# 16V2_EDA.net
KiCad netlist of a schematic drawn in EasyEDA Pro
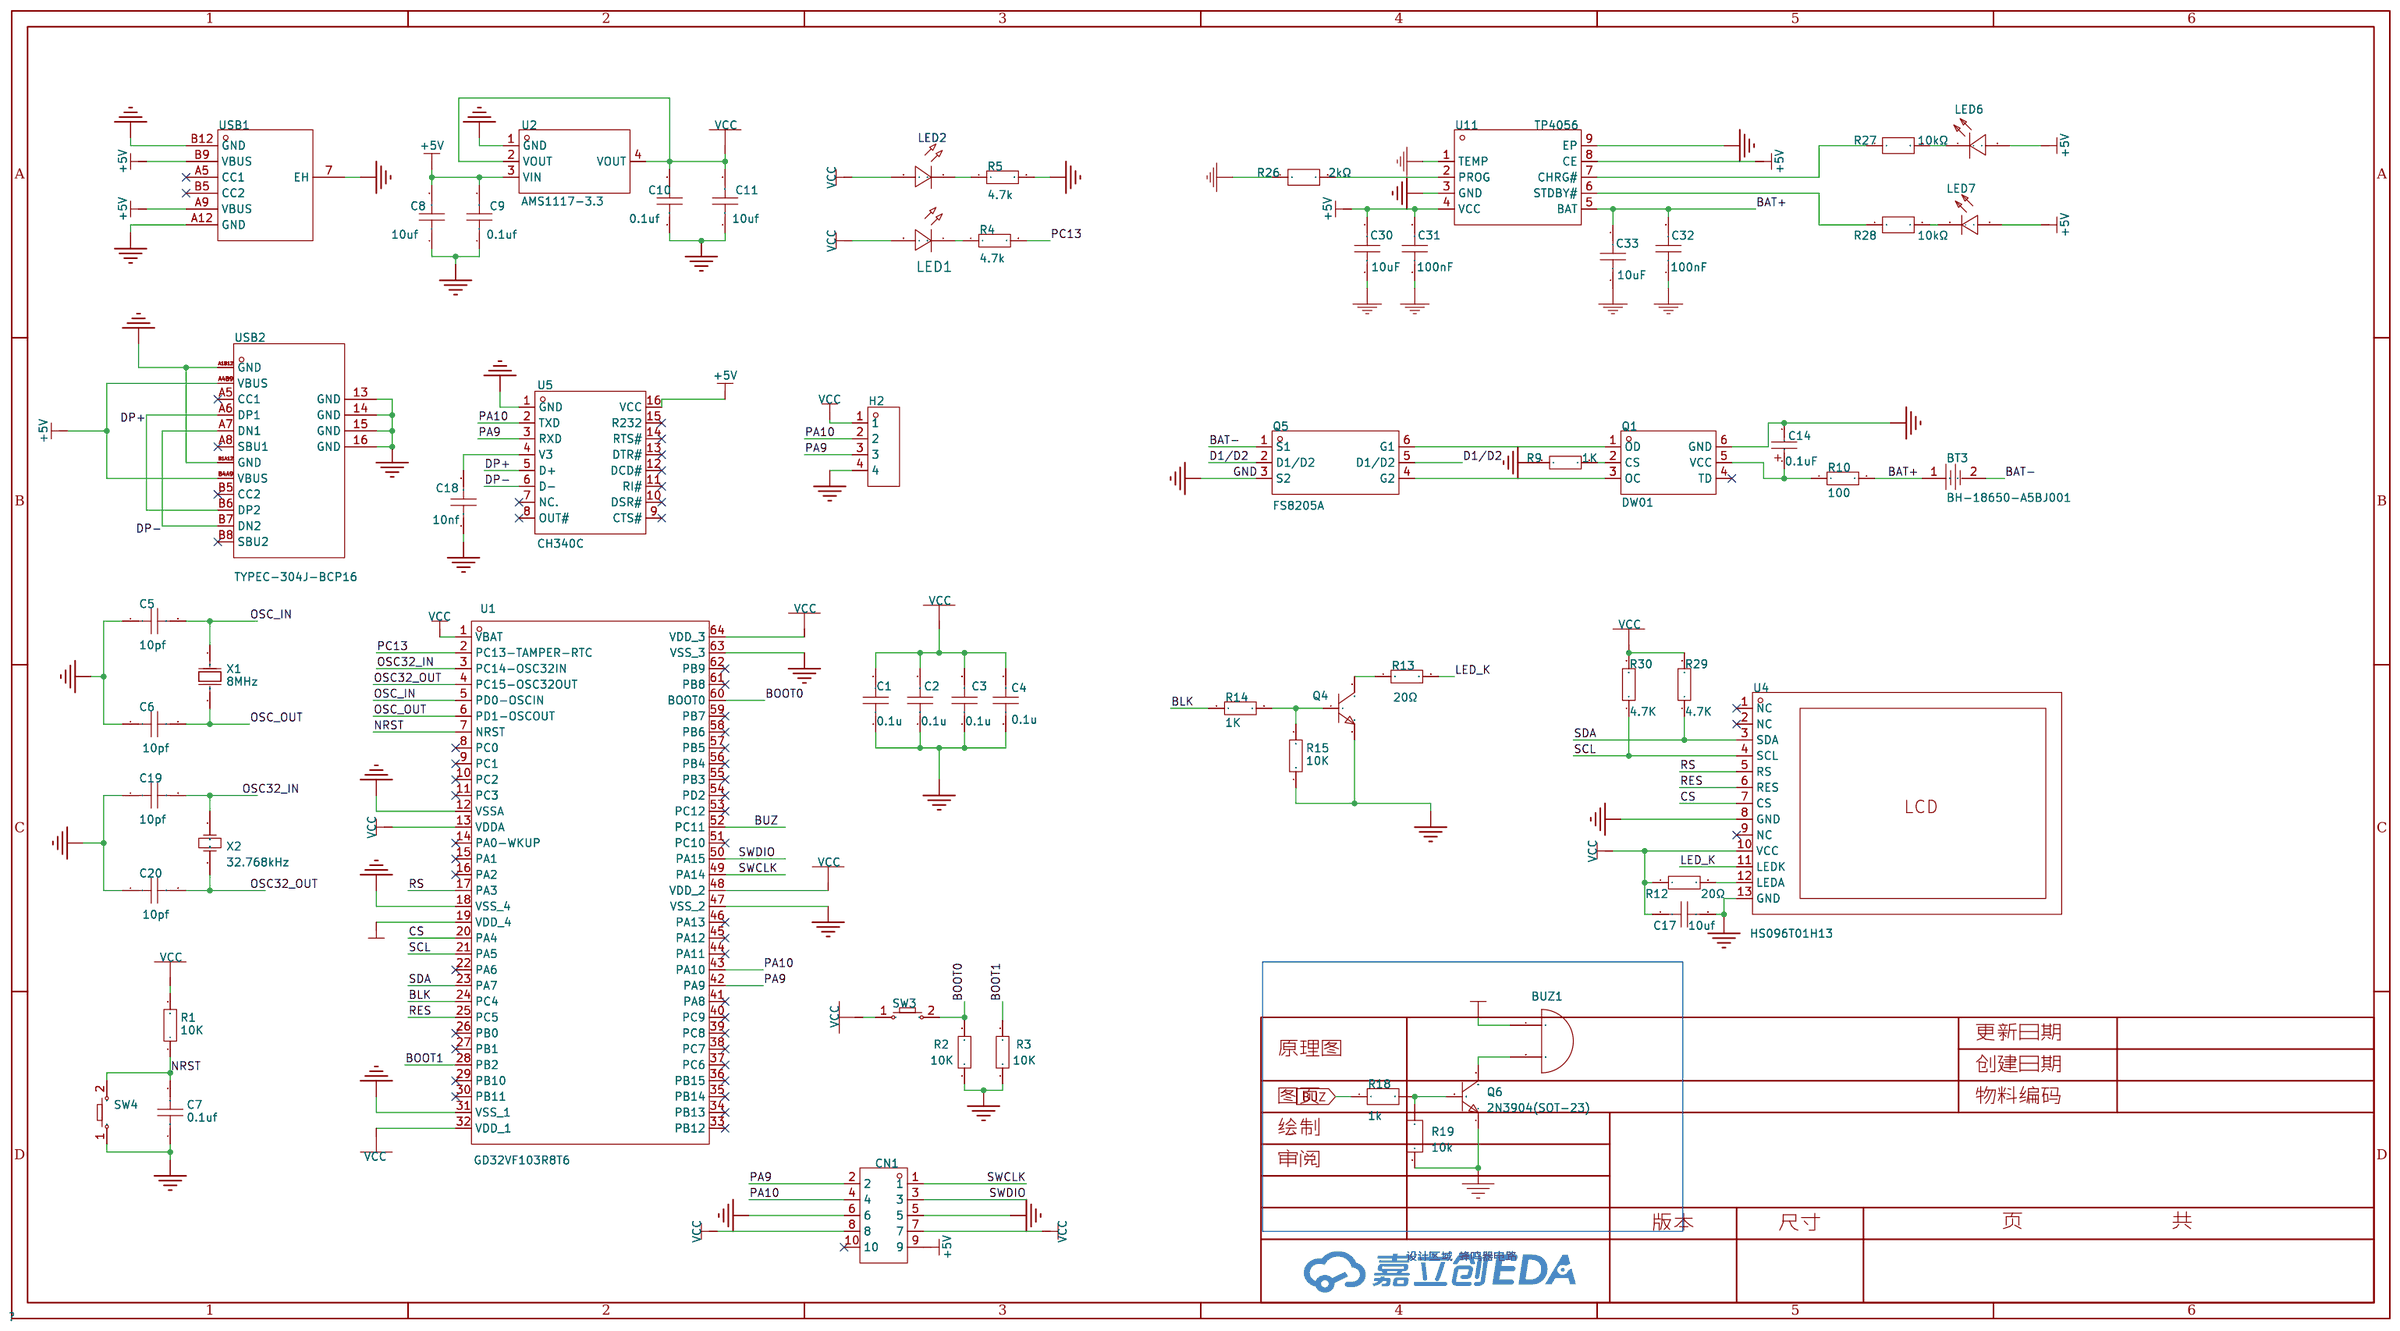
[diagram p0: schematic sheet]

(export (version "E")
  (design (tool "Eeschema 10.0.6"))
  (components
    (comp (ref "BT3")
      (value "BH-18650-A5BJ001")
      (footprint "easyedapro:BAT-TH_18650-A5BJ001")
      (description "BHNi DIP 适用电池18650电芯//电池底座/卧式DIP 电池盒/电池座 材质：PP  镀镍 ，")
      (fields (field (name "Manufacturer") "MYOUNG(美阳)"))
      (libsource (lib "easyedapro") (part "BH-18650-A5BJ001"))
    )
    (comp (ref "BUZ1") (value "BUZ1") (libsource (lib "easyedapro") (part "BUZ1")))
    (comp (ref "C1")
      (value "0.1u")
      (footprint "easyedapro:C0603")
      (libsource (lib "easyedapro") (part "capacitance"))
    )
    (comp (ref "C2")
      (value "0.1u")
      (footprint "easyedapro:C0603")
      (libsource (lib "easyedapro") (part "capacitance"))
    )
    (comp (ref "C3")
      (value "0.1u")
      (footprint "easyedapro:C0603")
      (libsource (lib "easyedapro") (part "capacitance"))
    )
    (comp (ref "C4")
      (value "0.1u")
      (footprint "easyedapro:C0603")
      (libsource (lib "easyedapro") (part "capacitance"))
    )
    (comp (ref "C5")
      (value "10pf")
      (footprint "easyedapro:C0603")
      (libsource (lib "easyedapro") (part "capacitance"))
    )
    (comp (ref "C6")
      (value "10pf")
      (footprint "easyedapro:C0603")
      (libsource (lib "easyedapro") (part "capacitance"))
    )
    (comp (ref "C7")
      (value "0.1uf")
      (footprint "easyedapro:C0603")
      (libsource (lib "easyedapro") (part "capacitance"))
    )
    (comp (ref "C8")
      (value "10uf")
      (footprint "easyedapro:C0603")
      (libsource (lib "easyedapro") (part "capacitance"))
    )
    (comp (ref "C9")
      (value "0.1uf")
      (footprint "easyedapro:C0603")
      (libsource (lib "easyedapro") (part "capacitance"))
    )
    (comp (ref "C10")
      (value "0.1uf")
      (footprint "easyedapro:C0603")
      (libsource (lib "easyedapro") (part "capacitance"))
    )
    (comp (ref "C11")
      (value "10uf")
      (footprint "easyedapro:C0603")
      (libsource (lib "easyedapro") (part "capacitance"))
    )
    (comp (ref "C14")
      (value "0.1uF")
      (footprint "easyedapro:C_Ele_SMD_3x5.4mm")
      (libsource (lib "easyedapro") (part "CAP"))
    )
    (comp (ref "C17")
      (value "10uf")
      (footprint "easyedapro:C0603")
      (libsource (lib "easyedapro") (part "capacitance"))
    )
    (comp (ref "C18")
      (value "10nf")
      (footprint "easyedapro:C0603")
      (libsource (lib "easyedapro") (part "capacitance"))
    )
    (comp (ref "C19")
      (value "10pf")
      (footprint "easyedapro:C0603")
      (libsource (lib "easyedapro") (part "capacitance"))
    )
    (comp (ref "C20")
      (value "10pf")
      (footprint "easyedapro:C0603")
      (libsource (lib "easyedapro") (part "capacitance"))
    )
    (comp (ref "C30")
      (value "10uF")
      (fields (field (name "Manufacturer") "SAMSUNG(三星)"))
      (libsource (lib "easyedapro") (part "10u"))
    )
    (comp (ref "C31")
      (value "100nF")
      (fields (field (name "Manufacturer") "YAGEO(国巨)"))
      (libsource (lib "easyedapro") (part "0.1u"))
    )
    (comp (ref "C32")
      (value "100nF")
      (fields (field (name "Manufacturer") "YAGEO(国巨)"))
      (libsource (lib "easyedapro") (part "0.1u"))
    )
    (comp (ref "C33")
      (value "10uF")
      (fields (field (name "Manufacturer") "SAMSUNG(三星)"))
      (libsource (lib "easyedapro") (part "10u"))
    )
    (comp (ref "CN1") (value "ZX-PZ2.54-2-5PZZ") (libsource (lib "easyedapro") (part "phd-2*5a_c2847737")))
    (comp (ref "H2")
      (value "2.54-1*4P反弯排针")
      (footprint "easyedapro:HDR-TH_4P-P2.54-H-M-W10.4")
      (fields (field (name "Manufacturer") "BOOMELE(博穆精密)"))
      (libsource (lib "easyedapro") (part "2.54-1*4P反弯排针"))
    )
    (comp (ref "LED1")
      (value "~")
      (footprint "easyedapro:LED_0603")
      (libsource (lib "easyedapro") (part "LED_R"))
    )
    (comp (ref "LED2")
      (value "~")
      (footprint "easyedapro:LED_0603")
      (libsource (lib "easyedapro") (part "LED_G"))
    )
    (comp (ref "LED6")
      (value "KT-0603R")
      (fields (field (name "Manufacturer") "KENTO"))
      (libsource (lib "easyedapro") (part "KT-0603R"))
    )
    (comp (ref "LED7") (value "NCD0603B1") (libsource (lib "easyedapro") (part "fc-da1608bk-470h10")))
    (comp (ref "Q1")
      (value "DW01")
      (footprint "easyedapro:SOT-23-6_L2.9-W1.6-P0.95-LS2.8-BR")
      (fields (field (name "Manufacturer") "Hottech(合科泰)"))
      (libsource (lib "easyedapro") (part "DW01"))
    )
    (comp (ref "Q4")
      (value "~")
      (footprint "easyedapro:S8050_SOT-23")
      (libsource (lib "easyedapro") (part "NPN"))
    )
    (comp (ref "Q5")
      (value "FS8205A")
      (footprint "easyedapro:SOT-23-6_L2.9-W1.6-P0.95-LS2.8-BR")
      (fields (field (name "Manufacturer") "TECH PUBLIC(台舟)"))
      (libsource (lib "easyedapro") (part "FS8205A_C2830320"))
    )
    (comp (ref "Q6")
      (value "2N3904(SOT-23)")
      (fields (field (name "Manufacturer Part") "2n3904S-RTK/PS") (field (name "Manufacturer") "KEC"))
      (libsource (lib "easyedapro") (part "2N3904(SOT-23)"))
    )
    (comp (ref "R1") (value "10K") (libsource (lib "easyedapro") (part "电阻")))
    (comp (ref "R2") (value "10K") (libsource (lib "easyedapro") (part "电阻")))
    (comp (ref "R3") (value "10K") (libsource (lib "easyedapro") (part "电阻")))
    (comp (ref "R4") (value "4.7k") (libsource (lib "easyedapro") (part "电阻")))
    (comp (ref "R5") (value "4.7k") (libsource (lib "easyedapro") (part "电阻")))
    (comp (ref "R9") (value "1K") (libsource (lib "easyedapro") (part "电阻")))
    (comp (ref "R10") (value "100") (libsource (lib "easyedapro") (part "电阻")))
    (comp (ref "R12") (value "20Ω") (libsource (lib "easyedapro") (part "电阻")))
    (comp (ref "R13") (value "20Ω") (libsource (lib "easyedapro") (part "电阻")))
    (comp (ref "R14") (value "1K") (libsource (lib "easyedapro") (part "电阻")))
    (comp (ref "R15") (value "10K") (libsource (lib "easyedapro") (part "电阻")))
    (comp (ref "R18") (value "1k") (libsource (lib "easyedapro") (part "1k")))
    (comp (ref "R19") (value "10k") (libsource (lib "easyedapro") (part "10k")))
    (comp (ref "R26")
      (value "2kΩ")
      (fields (field (name "Manufacturer") "UNI-ROYAL(厚声)"))
      (libsource (lib "easyedapro") (part "2k"))
    )
    (comp (ref "R27")
      (value "10kΩ")
      (fields (field (name "Manufacturer") "UNI-ROYAL(厚声)"))
      (libsource (lib "easyedapro") (part "10k"))
    )
    (comp (ref "R28")
      (value "10kΩ")
      (fields (field (name "Manufacturer") "UNI-ROYAL(厚声)"))
      (libsource (lib "easyedapro") (part "10k"))
    )
    (comp (ref "R29")
      (value "4.7K")
      (footprint "easyedapro:R0603")
      (libsource (lib "easyedapro") (part "电阻"))
    )
    (comp (ref "R30")
      (value "4.7K")
      (footprint "easyedapro:R0603")
      (libsource (lib "easyedapro") (part "电阻"))
    )
    (comp (ref "SW3")
      (value "~")
      (footprint "easyedapro:Key_SMD_3x4x2")
      (libsource (lib "easyedapro") (part "轻触按键x2"))
    )
    (comp (ref "SW4")
      (value "~")
      (footprint "easyedapro:Key_SMD_3x4x2")
      (libsource (lib "easyedapro") (part "轻触按键x2"))
    )
    (comp (ref "U1")
      (value "GD32VF103R8T6")
      (footprint "easyedapro:LQFP-64_L10.0-W10.0-P0.50-LS12.0-BL")
      (description "CPU内核:RISC-V;程序存储容量:64KB;RAM总容量:20KB;GPIO端口数量:51;工作电压范围:-;CPU最大主频:108MHz;程序存储器类型:FLASH;")
      (fields (field (name "Manufacturer") "GigaDevice(兆易创新)"))
      (libsource (lib "easyedapro") (part "GD32VF103R8T6"))
    )
    (comp (ref "U2")
      (value "AMS1117-3.3")
      (footprint "easyedapro:SOT-223-3_L6.5-W3.4-P2.30-LS7.0-BR")
      (description "输出类型:固定;最大输入电压:-;输出电压:3.3V;最大输出电流:1A;电源纹波抑制比(PSRR):72dB@(120Hz);输出极性:正极;")
      (fields (field (name "Manufacturer") "AMS"))
      (libsource (lib "easyedapro") (part "AMS1117-3.3"))
    )
    (comp (ref "U4")
      (value "HS096T01H13")
      (footprint "easyedapro:LCD-SMD_HS096T01H13")
      (description "主控芯片:ST7735;尺寸(inch):0.96;")
      (fields (field (name "Manufacturer") "HS(汉昇)"))
      (libsource (lib "easyedapro") (part "HS096T01H13"))
    )
    (comp (ref "U5")
      (value "CH340C")
      (footprint "easyedapro:SOP-16_L10.0-W3.9-P1.27-LS6.0-BL")
      (description "应用功能:收发器;接口协议:USB 2.0;数据速率:2Mbps;")
      (fields (field (name "Manufacturer") "WCH(南京沁恒)"))
      (libsource (lib "easyedapro") (part "CH340C"))
    )
    (comp (ref "U11")
      (value "TP4056")
      (fields (field (name "Manufacturer") "UMW(友台半导体)"))
      (libsource (lib "easyedapro") (part "TP4056_C725790"))
    )
    (comp (ref "USB1")
      (value "TYPE-C 6P")
      (footprint "easyedapro:TYPE-C-SMD_TYPE-C-6P")
      (description "连接器类型:Type-C;标准:-;公母:母;端口数量:1;触点数量:6P;安装方式:卧贴;额定电流 - 电源:-;工作温度范围:-40°C~+85°C;")
      (fields (field (name "Manufacturer") "SHOU HAN(首韩)"))
      (libsource (lib "easyedapro") (part "TYPE-C 6P"))
    )
    (comp (ref "USB2")
      (value "TYPEC-304J-BCP16")
      (footprint "easyedapro:USB-C-SMD_TYPEC-304J-BCP16")
      (fields (field (name "Manufacturer") "XUNPU(讯普)"))
      (libsource (lib "easyedapro") (part "TYPEC-304J-BCP16"))
    )
    (comp (ref "X1")
      (value "8MHz")
      (footprint "easyedapro:CRYSTAL-SMD_L11.5-W4.8-LS12.7")
      (description "晶振类型:贴片晶振;频率:8MHz;常温频差:±20ppm;外接负载电容:20pF;频率稳定度(全温):±30ppm;")
      (fields (field (name "Manufacturer Part") "X49SM8MSD2SC") (field (name "Manufacturer") "YXC(扬兴晶振)"))
      (libsource (lib "easyedapro") (part "X49SM8MSD2SC"))
    )
    (comp (ref "X2")
      (value "32.768kHz")
      (footprint "easyedapro:OSC-TH_BD3.1-P0.8-D0.3")
      (description "晶振类型:直插晶振;频率:32.768kHz;常温频差:±10ppm;外接负载电容:12.5pF;频率稳定度(全温):-;")
      (fields (field (name "Manufacturer Part") "X308032768KGB2SC") (field (name "Manufacturer") "YXC(扬兴晶振)"))
      (libsource (lib "easyedapro") (part "X308032768KGB2SC"))
    )
  )
  (nets
    (net (code "1") (name "+5V") (class "Default")
      (node (ref "C30") (pin "2") (pinfunction "2_2") (pintype "unspecified"))
      (node (ref "C31") (pin "2") (pinfunction "2_2") (pintype "unspecified"))
      (node (ref "C8") (pin "2") (pinfunction "2_2") (pintype "input"))
      (node (ref "C9") (pin "2") (pinfunction "2_2") (pintype "input"))
      (node (ref "CN1") (pin "9") (pinfunction "9_9") (pintype "unspecified"))
      (node (ref "LED6") (pin "2") (pinfunction "A_2") (pintype "unspecified"))
      (node (ref "LED7") (pin "2") (pinfunction "+_2") (pintype "input"))
      (node (ref "U11") (pin "4") (pinfunction "VCC_4") (pintype "unspecified"))
      (node (ref "U11") (pin "8") (pinfunction "CE_8") (pintype "unspecified"))
      (node (ref "U2") (pin "3") (pinfunction "VIN_3") (pintype "unspecified"))
      (node (ref "U5") (pin "16") (pinfunction "VCC_16") (pintype "unspecified"))
      (node (ref "USB1") (pin "A9") (pinfunction "VBUS_A9") (pintype "unspecified"))
      (node (ref "USB1") (pin "B9") (pinfunction "VBUS_B9") (pintype "unspecified"))
      (node (ref "USB2") (pin "A4B9") (pinfunction "VBUS_A4B9") (pintype "unspecified"))
      (node (ref "USB2") (pin "B4A9") (pinfunction "VBUS_B4A9") (pintype "unspecified"))
    )
    (net (code "2") (name "/BAT+") (class "Default")
      (node (ref "BT3") (pin "1") (pinfunction "1_1") (pintype "input"))
      (node (ref "C32") (pin "2") (pinfunction "2_2") (pintype "unspecified"))
      (node (ref "C33") (pin "2") (pinfunction "2_2") (pintype "unspecified"))
      (node (ref "R10") (pin "2") (pinfunction "2_2") (pintype "input"))
      (node (ref "U11") (pin "5") (pinfunction "BAT_5") (pintype "unspecified"))
    )
    (net (code "3") (name "/BAT-") (class "Default")
      (node (ref "BT3") (pin "2") (pinfunction "2_2") (pintype "input"))
      (node (ref "Q5") (pin "1") (pinfunction "S1_1") (pintype "unspecified"))
    )
    (net (code "4") (name "/BLK") (class "Default")
      (node (ref "R14") (pin "1") (pinfunction "1_1") (pintype "input"))
      (node (ref "U1") (pin "24") (pinfunction "PC4_24") (pintype "input"))
    )
    (net (code "5") (name "/BOOT0") (class "Default")
      (node (ref "R2") (pin "2") (pinfunction "2_2") (pintype "input"))
      (node (ref "SW3") (pin "2") (pinfunction "2_2") (pintype "input"))
      (node (ref "U1") (pin "60") (pinfunction "BOOT0_60") (pintype "input"))
    )
    (net (code "6") (name "/BOOT1") (class "Default")
      (node (ref "R3") (pin "2") (pinfunction "2_2") (pintype "input"))
      (node (ref "U1") (pin "28") (pinfunction "PB2_28") (pintype "input"))
    )
    (net (code "7") (name "/CS") (class "Default")
      (node (ref "U1") (pin "20") (pinfunction "PA4_20") (pintype "input"))
      (node (ref "U4") (pin "7") (pinfunction "CS_7") (pintype "unspecified"))
    )
    (net (code "8") (name "/D1{slash}D2") (class "Default")
      (node (ref "Q5") (pin "2") (pinfunction "D1/D2_2") (pintype "unspecified"))
      (node (ref "Q5") (pin "5") (pinfunction "D1/D2_5") (pintype "unspecified"))
    )
    (net (code "9") (name "/DP+") (class "Default")
      (node (ref "U5") (pin "5") (pinfunction "D+_5") (pintype "unspecified"))
      (node (ref "USB2") (pin "A6") (pinfunction "DP1_A6") (pintype "unspecified"))
      (node (ref "USB2") (pin "B6") (pinfunction "DP2_B6") (pintype "unspecified"))
    )
    (net (code "10") (name "/DP-") (class "Default")
      (node (ref "U5") (pin "6") (pinfunction "D-_6") (pintype "unspecified"))
      (node (ref "USB2") (pin "A7") (pinfunction "DN1_A7") (pintype "unspecified"))
      (node (ref "USB2") (pin "B7") (pinfunction "DN2_B7") (pintype "unspecified"))
    )
    (net (code "11") (name "/LED_K") (class "Default")
      (node (ref "R13") (pin "2") (pinfunction "2_2") (pintype "input"))
      (node (ref "U4") (pin "11") (pinfunction "LEDK_11") (pintype "unspecified"))
    )
    (net (code "12") (name "/NRST") (class "Default")
      (node (ref "C7") (pin "2") (pinfunction "2_2") (pintype "input"))
      (node (ref "R1") (pin "1") (pinfunction "1_1") (pintype "input"))
      (node (ref "SW4") (pin "2") (pinfunction "2_2") (pintype "input"))
      (node (ref "U1") (pin "7") (pinfunction "NRST_7") (pintype "input"))
    )
    (net (code "13") (name "/OSC32_IN") (class "Default")
      (node (ref "C19") (pin "2") (pinfunction "2_2") (pintype "input"))
      (node (ref "U1") (pin "3") (pinfunction "PC14-OSC32IN_3") (pintype "input"))
      (node (ref "X2") (pin "1") (pinfunction "OSC1_1") (pintype "unspecified"))
    )
    (net (code "14") (name "/OSC32_OUT") (class "Default")
      (node (ref "C20") (pin "2") (pinfunction "2_2") (pintype "input"))
      (node (ref "U1") (pin "4") (pinfunction "PC15-OSC32OUT_4") (pintype "input"))
      (node (ref "X2") (pin "2") (pinfunction "OSC2_2") (pintype "unspecified"))
    )
    (net (code "15") (name "/OSC_IN") (class "Default")
      (node (ref "C5") (pin "2") (pinfunction "2_2") (pintype "input"))
      (node (ref "U1") (pin "5") (pinfunction "PD0-OSCIN_5") (pintype "input"))
      (node (ref "X1") (pin "1") (pinfunction "OSC1_1") (pintype "input"))
    )
    (net (code "16") (name "/OSC_OUT") (class "Default")
      (node (ref "C6") (pin "2") (pinfunction "2_2") (pintype "input"))
      (node (ref "U1") (pin "6") (pinfunction "PD1-OSCOUT_6") (pintype "input"))
      (node (ref "X1") (pin "2") (pinfunction "OSC2_2") (pintype "input"))
    )
    (net (code "17") (name "/PA9") (class "Default")
      (node (ref "CN1") (pin "2") (pinfunction "2_2") (pintype "unspecified"))
      (node (ref "H2") (pin "3") (pinfunction "3_3") (pintype "unspecified"))
      (node (ref "U1") (pin "42") (pinfunction "PA9_42") (pintype "input"))
      (node (ref "U5") (pin "3") (pinfunction "RXD_3") (pintype "unspecified"))
    )
    (net (code "18") (name "/PA10") (class "Default")
      (node (ref "CN1") (pin "4") (pinfunction "4_4") (pintype "unspecified"))
      (node (ref "H2") (pin "2") (pinfunction "2_2") (pintype "unspecified"))
      (node (ref "U1") (pin "43") (pinfunction "PA10_43") (pintype "input"))
      (node (ref "U5") (pin "2") (pinfunction "TXD_2") (pintype "unspecified"))
    )
    (net (code "19") (name "/PC13") (class "Default")
      (node (ref "R4") (pin "2") (pinfunction "2_2") (pintype "input"))
      (node (ref "U1") (pin "2") (pinfunction "PC13-TAMPER-RTC_2") (pintype "input"))
    )
    (net (code "20") (name "/RES") (class "Default")
      (node (ref "U1") (pin "25") (pinfunction "PC5_25") (pintype "input"))
      (node (ref "U4") (pin "6") (pinfunction "RES_6") (pintype "unspecified"))
    )
    (net (code "21") (name "/RS") (class "Default")
      (node (ref "U1") (pin "17") (pinfunction "PA3_17") (pintype "input"))
      (node (ref "U4") (pin "5") (pinfunction "RS_5") (pintype "unspecified"))
    )
    (net (code "22") (name "/SCL") (class "Default")
      (node (ref "R30") (pin "1") (pinfunction "1_1") (pintype "input"))
      (node (ref "U1") (pin "21") (pinfunction "PA5_21") (pintype "input"))
      (node (ref "U4") (pin "4") (pinfunction "SCL_4") (pintype "unspecified"))
    )
    (net (code "23") (name "/SDA") (class "Default")
      (node (ref "R29") (pin "1") (pinfunction "1_1") (pintype "input"))
      (node (ref "U1") (pin "23") (pinfunction "PA7_23") (pintype "input"))
      (node (ref "U4") (pin "3") (pinfunction "SDA_3") (pintype "unspecified"))
    )
    (net (code "24") (name "/SWCLK") (class "Default")
      (node (ref "CN1") (pin "1") (pinfunction "1_1") (pintype "unspecified"))
      (node (ref "U1") (pin "49") (pinfunction "PA14_49") (pintype "input"))
    )
    (net (code "25") (name "/SWDIO") (class "Default")
      (node (ref "CN1") (pin "3") (pinfunction "3_3") (pintype "unspecified"))
      (node (ref "U1") (pin "50") (pinfunction "PA15_50") (pintype "input"))
    )
    (net (code "26") (name "BUZ") (class "Default")
      (node (ref "R18") (pin "1") (pinfunction "1_1") (pintype "input"))
      (node (ref "U1") (pin "52") (pinfunction "PC11_52") (pintype "input"))
    )
    (net (code "27") (name "GND") (class "Default")
      (node (ref "C1") (pin "1") (pinfunction "1_1") (pintype "input"))
      (node (ref "C10") (pin "1") (pinfunction "1_1") (pintype "input"))
      (node (ref "C11") (pin "1") (pinfunction "1_1") (pintype "input"))
      (node (ref "C14") (pin "2") (pinfunction "2_2") (pintype "input"))
      (node (ref "C17") (pin "2") (pinfunction "2_2") (pintype "input"))
      (node (ref "C18") (pin "1") (pinfunction "1_1") (pintype "input"))
      (node (ref "C19") (pin "1") (pinfunction "1_1") (pintype "input"))
      (node (ref "C2") (pin "1") (pinfunction "1_1") (pintype "input"))
      (node (ref "C20") (pin "1") (pinfunction "1_1") (pintype "input"))
      (node (ref "C3") (pin "1") (pinfunction "1_1") (pintype "input"))
      (node (ref "C30") (pin "1") (pinfunction "1_1") (pintype "unspecified"))
      (node (ref "C31") (pin "1") (pinfunction "1_1") (pintype "unspecified"))
      (node (ref "C32") (pin "1") (pinfunction "1_1") (pintype "unspecified"))
      (node (ref "C33") (pin "1") (pinfunction "1_1") (pintype "unspecified"))
      (node (ref "C4") (pin "1") (pinfunction "1_1") (pintype "input"))
      (node (ref "C5") (pin "1") (pinfunction "1_1") (pintype "input"))
      (node (ref "C6") (pin "1") (pinfunction "1_1") (pintype "input"))
      (node (ref "C7") (pin "1") (pinfunction "1_1") (pintype "input"))
      (node (ref "C8") (pin "1") (pinfunction "1_1") (pintype "input"))
      (node (ref "C9") (pin "1") (pinfunction "1_1") (pintype "input"))
      (node (ref "CN1") (pin "5") (pinfunction "5_5") (pintype "unspecified"))
      (node (ref "CN1") (pin "6") (pinfunction "6_6") (pintype "unspecified"))
      (node (ref "H2") (pin "4") (pinfunction "4_4") (pintype "unspecified"))
      (node (ref "Q1") (pin "6") (pinfunction "GND_6") (pintype "input"))
      (node (ref "Q4") (pin "2") (pinfunction "2_2") (pintype "unspecified"))
      (node (ref "Q5") (pin "3") (pinfunction "S2_3") (pintype "unspecified"))
      (node (ref "Q6") (pin "1") (pinfunction "E_1") (pintype "input"))
      (node (ref "R15") (pin "1") (pinfunction "1_1") (pintype "input"))
      (node (ref "R19") (pin "1") (pinfunction "1_1") (pintype "unspecified"))
      (node (ref "R2") (pin "1") (pinfunction "1_1") (pintype "input"))
      (node (ref "R26") (pin "1") (pinfunction "1_1") (pintype "unspecified"))
      (node (ref "R3") (pin "1") (pinfunction "1_1") (pintype "input"))
      (node (ref "R5") (pin "2") (pinfunction "2_2") (pintype "input"))
      (node (ref "R9") (pin "1") (pinfunction "1_1") (pintype "input"))
      (node (ref "SW4") (pin "1") (pinfunction "1_1") (pintype "input"))
      (node (ref "U1") (pin "12") (pinfunction "VSSA_12") (pintype "input"))
      (node (ref "U1") (pin "18") (pinfunction "VSS_4_18") (pintype "input"))
      (node (ref "U1") (pin "31") (pinfunction "VSS_1_31") (pintype "input"))
      (node (ref "U1") (pin "47") (pinfunction "VSS_2_47") (pintype "input"))
      (node (ref "U1") (pin "63") (pinfunction "VSS_3_63") (pintype "input"))
      (node (ref "U11") (pin "1") (pinfunction "TEMP_1") (pintype "unspecified"))
      (node (ref "U11") (pin "3") (pinfunction "GND_3") (pintype "unspecified"))
      (node (ref "U11") (pin "9") (pinfunction "EP_9") (pintype "unspecified"))
      (node (ref "U2") (pin "1") (pinfunction "GND_1") (pintype "unspecified"))
      (node (ref "U4") (pin "13") (pinfunction "GND_13") (pintype "unspecified"))
      (node (ref "U4") (pin "8") (pinfunction "GND_8") (pintype "unspecified"))
      (node (ref "U5") (pin "1") (pinfunction "GND_1") (pintype "unspecified"))
      (node (ref "USB1") (pin "7") (pinfunction "EH_7") (pintype "unspecified"))
      (node (ref "USB1") (pin "A12") (pinfunction "GND_A12") (pintype "unspecified"))
      (node (ref "USB1") (pin "B12") (pinfunction "GND_B12") (pintype "unspecified"))
      (node (ref "USB2") (pin "13") (pinfunction "GND_13") (pintype "unspecified"))
      (node (ref "USB2") (pin "14") (pinfunction "GND_14") (pintype "unspecified"))
      (node (ref "USB2") (pin "15") (pinfunction "GND_15") (pintype "unspecified"))
      (node (ref "USB2") (pin "16") (pinfunction "GND_16") (pintype "unspecified"))
      (node (ref "USB2") (pin "A1B12") (pinfunction "GND_A1B12") (pintype "unspecified"))
      (node (ref "USB2") (pin "B1A12") (pinfunction "GND_B1A12") (pintype "unspecified"))
    )
    (net (code "28") (name "Net-(BUZ1-B)") (class "Default")
      (node (ref "BUZ1") (pin "2") (pinfunction "B_2") (pintype "input"))
      (node (ref "Q6") (pin "3") (pinfunction "C_3") (pintype "input"))
    )
    (net (code "29") (name "Net-(LED1-C)") (class "Default")
      (node (ref "LED1") (pin "1") (pinfunction "C_1") (pintype "input"))
      (node (ref "R4") (pin "1") (pinfunction "1_1") (pintype "input"))
    )
    (net (code "30") (name "Net-(LED2-C)") (class "Default")
      (node (ref "LED2") (pin "1") (pinfunction "C_1") (pintype "input"))
      (node (ref "R5") (pin "1") (pinfunction "1_1") (pintype "input"))
    )
    (net (code "31") (name "Net-(LED6-K)") (class "Default")
      (node (ref "LED6") (pin "1") (pinfunction "K_1") (pintype "unspecified"))
      (node (ref "R27") (pin "2") (pinfunction "2_2") (pintype "unspecified"))
    )
    (net (code "32") (name "Net-(LED7--)") (class "Default")
      (node (ref "LED7") (pin "1") (pinfunction "-_1") (pintype "input"))
      (node (ref "R28") (pin "2") (pinfunction "2_2") (pintype "unspecified"))
    )
    (net (code "33") (name "Net-(Q1-CS)") (class "Default")
      (node (ref "Q1") (pin "2") (pinfunction "CS_2") (pintype "input"))
      (node (ref "R9") (pin "2") (pinfunction "2_2") (pintype "input"))
    )
    (net (code "34") (name "Net-(Q1-OC)") (class "Default")
      (node (ref "Q1") (pin "3") (pinfunction "OC_3") (pintype "input"))
      (node (ref "Q5") (pin "4") (pinfunction "G2_4") (pintype "unspecified"))
    )
    (net (code "35") (name "Net-(Q1-OD)") (class "Default")
      (node (ref "Q1") (pin "1") (pinfunction "OD_1") (pintype "input"))
      (node (ref "Q5") (pin "6") (pinfunction "G1_6") (pintype "unspecified"))
    )
    (net (code "36") (name "Net-(Q1-VCC)") (class "Default")
      (node (ref "C14") (pin "1") (pinfunction "1_1") (pintype "input"))
      (node (ref "Q1") (pin "5") (pinfunction "VCC_5") (pintype "input"))
      (node (ref "R10") (pin "1") (pinfunction "1_1") (pintype "input"))
    )
    (net (code "37") (name "Net-(Q4-Pad1)") (class "Default")
      (node (ref "Q4") (pin "1") (pinfunction "1_1") (pintype "unspecified"))
      (node (ref "R14") (pin "2") (pinfunction "2_2") (pintype "input"))
      (node (ref "R15") (pin "2") (pinfunction "2_2") (pintype "input"))
    )
    (net (code "38") (name "Net-(Q4-Pad3)") (class "Default")
      (node (ref "Q4") (pin "3") (pinfunction "3_3") (pintype "unspecified"))
      (node (ref "R13") (pin "1") (pinfunction "1_1") (pintype "input"))
    )
    (net (code "39") (name "Net-(Q6-B)") (class "Default")
      (node (ref "Q6") (pin "2") (pinfunction "B_2") (pintype "input"))
      (node (ref "R18") (pin "2") (pinfunction "2_2") (pintype "input"))
      (node (ref "R19") (pin "2") (pinfunction "2_2") (pintype "unspecified"))
    )
    (net (code "40") (name "Net-(U4-LEDA)") (class "Default")
      (node (ref "R12") (pin "2") (pinfunction "2_2") (pintype "input"))
      (node (ref "U4") (pin "12") (pinfunction "LEDA_12") (pintype "unspecified"))
    )
    (net (code "41") (name "Net-(U5-V3)") (class "Default")
      (node (ref "C18") (pin "2") (pinfunction "2_2") (pintype "input"))
      (node (ref "U5") (pin "4") (pinfunction "V3_4") (pintype "unspecified"))
    )
    (net (code "42") (name "Net-(U11-CHRG#)") (class "Default")
      (node (ref "R27") (pin "1") (pinfunction "1_1") (pintype "unspecified"))
      (node (ref "U11") (pin "7") (pinfunction "CHRG#_7") (pintype "unspecified"))
    )
    (net (code "43") (name "Net-(U11-PROG)") (class "Default")
      (node (ref "R26") (pin "2") (pinfunction "2_2") (pintype "unspecified"))
      (node (ref "U11") (pin "2") (pinfunction "PROG_2") (pintype "unspecified"))
    )
    (net (code "44") (name "Net-(U11-STDBY#)") (class "Default")
      (node (ref "R28") (pin "1") (pinfunction "1_1") (pintype "unspecified"))
      (node (ref "U11") (pin "6") (pinfunction "STDBY#_6") (pintype "unspecified"))
    )
    (net (code "45") (name "VCC") (class "Default")
      (node (ref "BUZ1") (pin "1") (pinfunction "A_1") (pintype "input"))
      (node (ref "C1") (pin "2") (pinfunction "2_2") (pintype "input"))
      (node (ref "C10") (pin "2") (pinfunction "2_2") (pintype "input"))
      (node (ref "C11") (pin "2") (pinfunction "2_2") (pintype "input"))
      (node (ref "C17") (pin "1") (pinfunction "1_1") (pintype "input"))
      (node (ref "C2") (pin "2") (pinfunction "2_2") (pintype "input"))
      (node (ref "C3") (pin "2") (pinfunction "2_2") (pintype "input"))
      (node (ref "C4") (pin "2") (pinfunction "2_2") (pintype "input"))
      (node (ref "CN1") (pin "7") (pinfunction "7_7") (pintype "unspecified"))
      (node (ref "CN1") (pin "8") (pinfunction "8_8") (pintype "unspecified"))
      (node (ref "H2") (pin "1") (pinfunction "1_1") (pintype "unspecified"))
      (node (ref "LED1") (pin "2") (pinfunction "A_2") (pintype "input"))
      (node (ref "LED2") (pin "2") (pinfunction "A_2") (pintype "input"))
      (node (ref "R1") (pin "2") (pinfunction "2_2") (pintype "input"))
      (node (ref "R12") (pin "1") (pinfunction "1_1") (pintype "input"))
      (node (ref "R29") (pin "2") (pinfunction "2_2") (pintype "input"))
      (node (ref "R30") (pin "2") (pinfunction "2_2") (pintype "input"))
      (node (ref "SW3") (pin "1") (pinfunction "1_1") (pintype "input"))
      (node (ref "U1") (pin "1") (pinfunction "VBAT_1") (pintype "input"))
      (node (ref "U1") (pin "13") (pinfunction "VDDA_13") (pintype "input"))
      (node (ref "U1") (pin "19") (pinfunction "VDD_4_19") (pintype "input"))
      (node (ref "U1") (pin "32") (pinfunction "VDD_1_32") (pintype "input"))
      (node (ref "U1") (pin "48") (pinfunction "VDD_2_48") (pintype "input"))
      (node (ref "U1") (pin "64") (pinfunction "VDD_3_64") (pintype "input"))
      (node (ref "U2") (pin "2") (pinfunction "VOUT_2") (pintype "unspecified"))
      (node (ref "U2") (pin "4") (pinfunction "VOUT_4") (pintype "unspecified"))
      (node (ref "U4") (pin "10") (pinfunction "VCC_10") (pintype "unspecified"))
    )
    (net (code "46") (name "unconnected-(CN1-Pad10)") (class "Default")
      (node (ref "CN1") (pin "10") (pinfunction "10_10") (pintype "unspecified+no_connect"))
    )
    (net (code "47") (name "unconnected-(Q1-TD-Pad4)") (class "Default")
      (node (ref "Q1") (pin "4") (pinfunction "TD_4") (pintype "input+no_connect"))
    )
    (net (code "48") (name "unconnected-(U1-PA0-WKUP-Pad14)") (class "Default")
      (node (ref "U1") (pin "14") (pinfunction "PA0-WKUP_14") (pintype "input+no_connect"))
    )
    (net (code "49") (name "unconnected-(U1-PA1-Pad15)") (class "Default")
      (node (ref "U1") (pin "15") (pinfunction "PA1_15") (pintype "input+no_connect"))
    )
    (net (code "50") (name "unconnected-(U1-PA2-Pad16)") (class "Default")
      (node (ref "U1") (pin "16") (pinfunction "PA2_16") (pintype "input+no_connect"))
    )
    (net (code "51") (name "unconnected-(U1-PA6-Pad22)") (class "Default")
      (node (ref "U1") (pin "22") (pinfunction "PA6_22") (pintype "input+no_connect"))
    )
    (net (code "52") (name "unconnected-(U1-PA8-Pad41)") (class "Default")
      (node (ref "U1") (pin "41") (pinfunction "PA8_41") (pintype "input+no_connect"))
    )
    (net (code "53") (name "unconnected-(U1-PA11-Pad44)") (class "Default")
      (node (ref "U1") (pin "44") (pinfunction "PA11_44") (pintype "input+no_connect"))
    )
    (net (code "54") (name "unconnected-(U1-PA12-Pad45)") (class "Default")
      (node (ref "U1") (pin "45") (pinfunction "PA12_45") (pintype "input+no_connect"))
    )
    (net (code "55") (name "unconnected-(U1-PA13-Pad46)") (class "Default")
      (node (ref "U1") (pin "46") (pinfunction "PA13_46") (pintype "input+no_connect"))
    )
    (net (code "56") (name "unconnected-(U1-PB0-Pad26)") (class "Default")
      (node (ref "U1") (pin "26") (pinfunction "PB0_26") (pintype "input+no_connect"))
    )
    (net (code "57") (name "unconnected-(U1-PB1-Pad27)") (class "Default")
      (node (ref "U1") (pin "27") (pinfunction "PB1_27") (pintype "input+no_connect"))
    )
    (net (code "58") (name "unconnected-(U1-PB3-Pad55)") (class "Default")
      (node (ref "U1") (pin "55") (pinfunction "PB3_55") (pintype "input+no_connect"))
    )
    (net (code "59") (name "unconnected-(U1-PB4-Pad56)") (class "Default")
      (node (ref "U1") (pin "56") (pinfunction "PB4_56") (pintype "input+no_connect"))
    )
    (net (code "60") (name "unconnected-(U1-PB5-Pad57)") (class "Default")
      (node (ref "U1") (pin "57") (pinfunction "PB5_57") (pintype "input+no_connect"))
    )
    (net (code "61") (name "unconnected-(U1-PB6-Pad58)") (class "Default")
      (node (ref "U1") (pin "58") (pinfunction "PB6_58") (pintype "input+no_connect"))
    )
    (net (code "62") (name "unconnected-(U1-PB7-Pad59)") (class "Default")
      (node (ref "U1") (pin "59") (pinfunction "PB7_59") (pintype "input+no_connect"))
    )
    (net (code "63") (name "unconnected-(U1-PB8-Pad61)") (class "Default")
      (node (ref "U1") (pin "61") (pinfunction "PB8_61") (pintype "input+no_connect"))
    )
    (net (code "64") (name "unconnected-(U1-PB9-Pad62)") (class "Default")
      (node (ref "U1") (pin "62") (pinfunction "PB9_62") (pintype "input+no_connect"))
    )
    (net (code "65") (name "unconnected-(U1-PB10-Pad29)") (class "Default")
      (node (ref "U1") (pin "29") (pinfunction "PB10_29") (pintype "input+no_connect"))
    )
    (net (code "66") (name "unconnected-(U1-PB11-Pad30)") (class "Default")
      (node (ref "U1") (pin "30") (pinfunction "PB11_30") (pintype "input+no_connect"))
    )
    (net (code "67") (name "unconnected-(U1-PB12-Pad33)") (class "Default")
      (node (ref "U1") (pin "33") (pinfunction "PB12_33") (pintype "input+no_connect"))
    )
    (net (code "68") (name "unconnected-(U1-PB13-Pad34)") (class "Default")
      (node (ref "U1") (pin "34") (pinfunction "PB13_34") (pintype "input+no_connect"))
    )
    (net (code "69") (name "unconnected-(U1-PB14-Pad35)") (class "Default")
      (node (ref "U1") (pin "35") (pinfunction "PB14_35") (pintype "input+no_connect"))
    )
    (net (code "70") (name "unconnected-(U1-PB15-Pad36)") (class "Default")
      (node (ref "U1") (pin "36") (pinfunction "PB15_36") (pintype "input+no_connect"))
    )
    (net (code "71") (name "unconnected-(U1-PC0-Pad8)") (class "Default")
      (node (ref "U1") (pin "8") (pinfunction "PC0_8") (pintype "input+no_connect"))
    )
    (net (code "72") (name "unconnected-(U1-PC1-Pad9)") (class "Default")
      (node (ref "U1") (pin "9") (pinfunction "PC1_9") (pintype "input+no_connect"))
    )
    (net (code "73") (name "unconnected-(U1-PC2-Pad10)") (class "Default")
      (node (ref "U1") (pin "10") (pinfunction "PC2_10") (pintype "input+no_connect"))
    )
    (net (code "74") (name "unconnected-(U1-PC3-Pad11)") (class "Default")
      (node (ref "U1") (pin "11") (pinfunction "PC3_11") (pintype "input+no_connect"))
    )
    (net (code "75") (name "unconnected-(U1-PC6-Pad37)") (class "Default")
      (node (ref "U1") (pin "37") (pinfunction "PC6_37") (pintype "input+no_connect"))
    )
    (net (code "76") (name "unconnected-(U1-PC7-Pad38)") (class "Default")
      (node (ref "U1") (pin "38") (pinfunction "PC7_38") (pintype "input+no_connect"))
    )
    (net (code "77") (name "unconnected-(U1-PC8-Pad39)") (class "Default")
      (node (ref "U1") (pin "39") (pinfunction "PC8_39") (pintype "input+no_connect"))
    )
    (net (code "78") (name "unconnected-(U1-PC9-Pad40)") (class "Default")
      (node (ref "U1") (pin "40") (pinfunction "PC9_40") (pintype "input+no_connect"))
    )
    (net (code "79") (name "unconnected-(U1-PC10-Pad51)") (class "Default")
      (node (ref "U1") (pin "51") (pinfunction "PC10_51") (pintype "input+no_connect"))
    )
    (net (code "80") (name "unconnected-(U1-PC12-Pad53)") (class "Default")
      (node (ref "U1") (pin "53") (pinfunction "PC12_53") (pintype "input+no_connect"))
    )
    (net (code "81") (name "unconnected-(U1-PD2-Pad54)") (class "Default")
      (node (ref "U1") (pin "54") (pinfunction "PD2_54") (pintype "input+no_connect"))
    )
    (net (code "82") (name "unconnected-(U4-NC-Pad1)") (class "Default")
      (node (ref "U4") (pin "1") (pinfunction "NC_1") (pintype "unspecified+no_connect"))
    )
    (net (code "83") (name "unconnected-(U4-NC-Pad2)") (class "Default")
      (node (ref "U4") (pin "2") (pinfunction "NC_2") (pintype "unspecified+no_connect"))
    )
    (net (code "84") (name "unconnected-(U4-NC-Pad9)") (class "Default")
      (node (ref "U4") (pin "9") (pinfunction "NC_9") (pintype "unspecified+no_connect"))
    )
    (net (code "85") (name "unconnected-(U5-CTS#-Pad9)") (class "Default")
      (node (ref "U5") (pin "9") (pinfunction "CTS#_9") (pintype "unspecified+no_connect"))
    )
    (net (code "86") (name "unconnected-(U5-DCD#-Pad12)") (class "Default")
      (node (ref "U5") (pin "12") (pinfunction "DCD#_12") (pintype "unspecified+no_connect"))
    )
    (net (code "87") (name "unconnected-(U5-DSR#-Pad10)") (class "Default")
      (node (ref "U5") (pin "10") (pinfunction "DSR#_10") (pintype "unspecified+no_connect"))
    )
    (net (code "88") (name "unconnected-(U5-DTR#-Pad13)") (class "Default")
      (node (ref "U5") (pin "13") (pinfunction "DTR#_13") (pintype "unspecified+no_connect"))
    )
    (net (code "89") (name "unconnected-(U5-NC.-Pad7)") (class "Default")
      (node (ref "U5") (pin "7") (pinfunction "NC._7") (pintype "unspecified+no_connect"))
    )
    (net (code "90") (name "unconnected-(U5-OUT#-Pad8)") (class "Default")
      (node (ref "U5") (pin "8") (pinfunction "OUT#_8") (pintype "unspecified+no_connect"))
    )
    (net (code "91") (name "unconnected-(U5-R232-Pad15)") (class "Default")
      (node (ref "U5") (pin "15") (pinfunction "R232_15") (pintype "unspecified+no_connect"))
    )
    (net (code "92") (name "unconnected-(U5-RI#-Pad11)") (class "Default")
      (node (ref "U5") (pin "11") (pinfunction "RI#_11") (pintype "unspecified+no_connect"))
    )
    (net (code "93") (name "unconnected-(U5-RTS#-Pad14)") (class "Default")
      (node (ref "U5") (pin "14") (pinfunction "RTS#_14") (pintype "unspecified+no_connect"))
    )
    (net (code "94") (name "unconnected-(USB1-CC1-PadA5)") (class "Default")
      (node (ref "USB1") (pin "A5") (pinfunction "CC1_A5") (pintype "unspecified+no_connect"))
    )
    (net (code "95") (name "unconnected-(USB1-CC2-PadB5)") (class "Default")
      (node (ref "USB1") (pin "B5") (pinfunction "CC2_B5") (pintype "unspecified+no_connect"))
    )
    (net (code "96") (name "unconnected-(USB2-CC1-PadA5)") (class "Default")
      (node (ref "USB2") (pin "A5") (pinfunction "CC1_A5") (pintype "unspecified+no_connect"))
    )
    (net (code "97") (name "unconnected-(USB2-CC2-PadB5)") (class "Default")
      (node (ref "USB2") (pin "B5") (pinfunction "CC2_B5") (pintype "unspecified+no_connect"))
    )
    (net (code "98") (name "unconnected-(USB2-SBU1-PadA8)") (class "Default")
      (node (ref "USB2") (pin "A8") (pinfunction "SBU1_A8") (pintype "unspecified+no_connect"))
    )
    (net (code "99") (name "unconnected-(USB2-SBU2-PadB8)") (class "Default")
      (node (ref "USB2") (pin "B8") (pinfunction "SBU2_B8") (pintype "unspecified+no_connect"))
    )
  )
)
